# Frame2TTL_v3_0_0.net
KiCad netlist of a schematic drawn in EAGLE
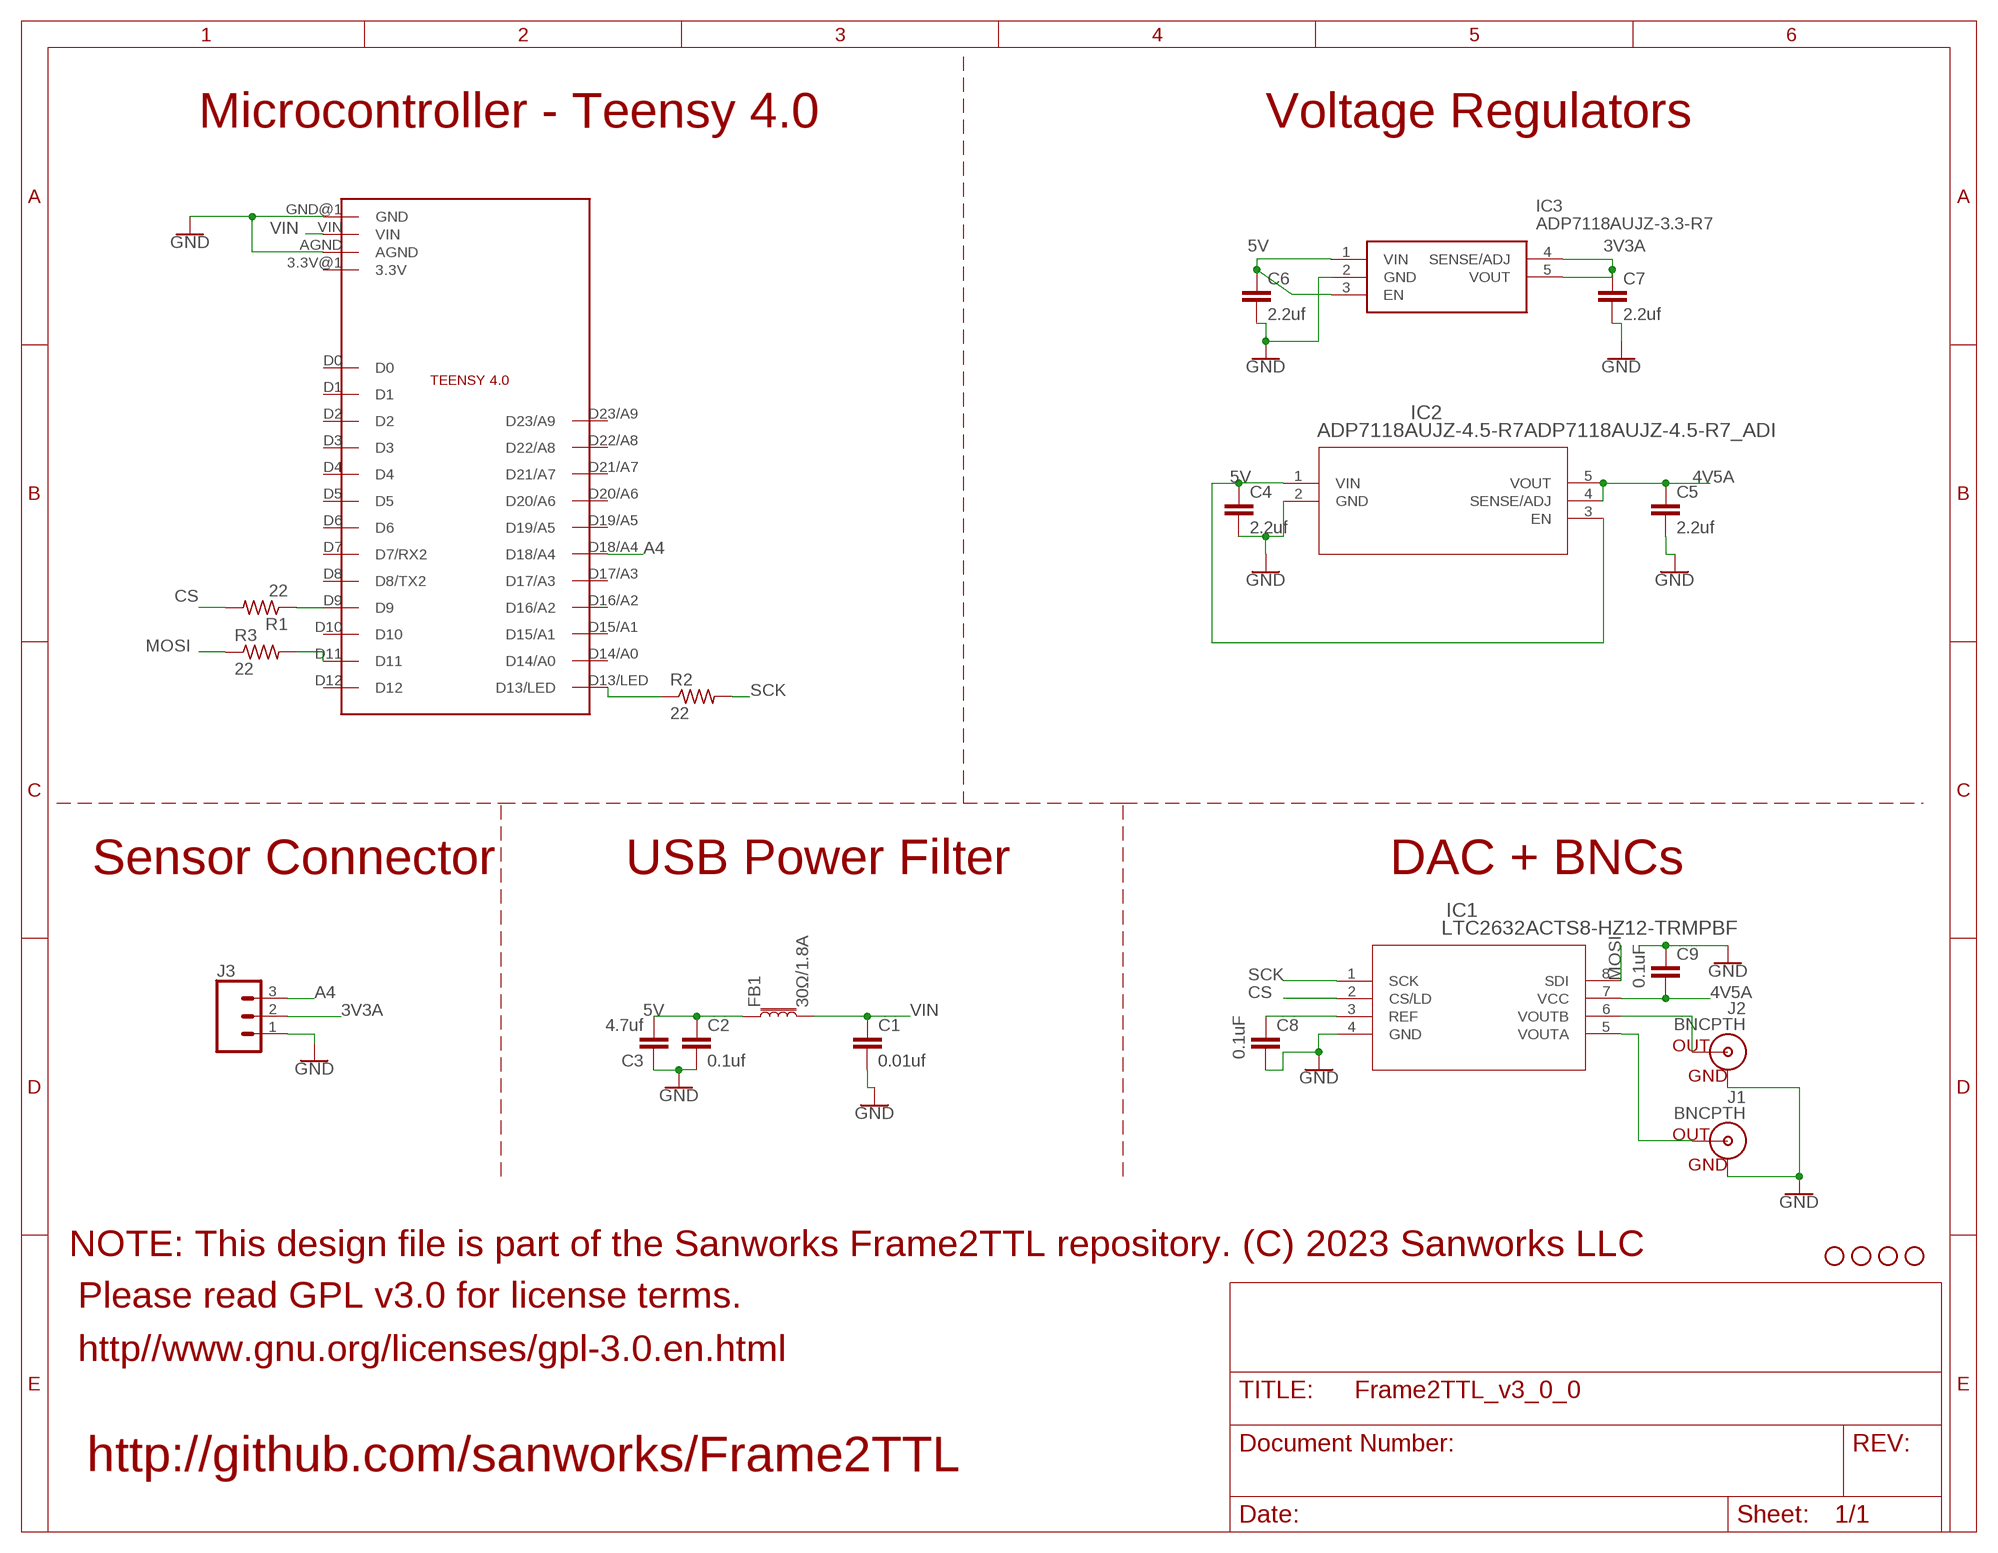
[diagram p0: schematic, sheet 1]

(export (version "E")
  (design (tool "Eeschema 10.0.6"))
  (components
    (comp (ref "C1")
      (value "0.01uf")
      (footprint "eagle-import:0805")
      (libsource (lib "eagle-import") (part "10UF-0805-10V-10%"))
    )
    (comp (ref "C2")
      (value "0.1uf")
      (footprint "eagle-import:0805")
      (libsource (lib "eagle-import") (part "10UF-0805-10V-10%"))
    )
    (comp (ref "C3")
      (value "4.7uf")
      (footprint "eagle-import:1206@2")
      (libsource (lib "eagle-import") (part "CAP1206"))
    )
    (comp (ref "C4")
      (value "2.2uf")
      (footprint "eagle-import:0805")
      (libsource (lib "eagle-import") (part "1.0UF-0805-25V-10%"))
    )
    (comp (ref "C5")
      (value "2.2uf")
      (footprint "eagle-import:0805")
      (libsource (lib "eagle-import") (part "1.0UF-0805-25V-10%"))
    )
    (comp (ref "C6")
      (value "2.2uf")
      (footprint "eagle-import:0805")
      (libsource (lib "eagle-import") (part "1.0UF-0805-25V-10%"))
    )
    (comp (ref "C7")
      (value "2.2uf")
      (footprint "eagle-import:0805")
      (libsource (lib "eagle-import") (part "1.0UF-0805-25V-10%"))
    )
    (comp (ref "C8")
      (value "0.1uF")
      (footprint "eagle-import:0805")
      (libsource (lib "eagle-import") (part "1.0UF-0805-25V-10%"))
    )
    (comp (ref "C9")
      (value "0.1uF")
      (footprint "eagle-import:0805")
      (libsource (lib "eagle-import") (part "1.0UF-0805-25V-10%"))
    )
    (comp (ref "FB1")
      (value "30Ω/1.8A")
      (footprint "eagle-import:0603")
      (libsource (lib "eagle-import") (part "FERRITE_BEAD-0603"))
    )
    (comp (ref "H1")
      (value "STAND-OFF")
      (footprint "eagle-import:STAND-OFF")
      (libsource (lib "eagle-import") (part "STAND-OFF"))
    )
    (comp (ref "H2")
      (value "STAND-OFF")
      (footprint "eagle-import:STAND-OFF")
      (libsource (lib "eagle-import") (part "STAND-OFF"))
    )
    (comp (ref "H3")
      (value "STAND-OFF")
      (footprint "eagle-import:STAND-OFF")
      (libsource (lib "eagle-import") (part "STAND-OFF"))
    )
    (comp (ref "H4")
      (value "STAND-OFF")
      (footprint "eagle-import:STAND-OFF")
      (libsource (lib "eagle-import") (part "STAND-OFF"))
    )
    (comp (ref "IC1")
      (value "LTC2632ACTS8-HZ12-TRMPBF")
      (footprint "eagle-import:TSOT-23-8_1P625X2P9_ADI")
      (fields
        (field (name "MANUFACTURER_PART_NUMBER") "LTC2632AHTS8-LI12#TRMPBF")
        (field (name "COPYRIGHT") "Copyright (C) 2022 Ultra Librarian. All rights reserved.")
      )
      (libsource (lib "eagle-import") (part "LTC2632AHTS8-LI12TRMPBF"))
    )
    (comp (ref "IC2")
      (value "ADP7118AUJZ-4.5-R7ADP7118AUJZ-4.5-R7_ADI")
      (footprint "eagle-import:ADP7118AUJZ-4.5-R7_ADI")
      (fields
        (field (name "MANUFACTURER_PART_NUMBER") "ADP7118AUJZ-4.5-R7")
        (field (name "COPYRIGHT") "Copyright (C) 2023 Ultra Librarian. All rights reserved.")
      )
      (libsource (lib "eagle-import") (part "ADP7118AUJZ-4.5-R7ADP7118AUJZ-4.5-R7_ADI"))
    )
    (comp (ref "IC3")
      (value "ADP7118AUJZ-3.3-R7")
      (footprint "eagle-import:SOT95P280X100-5N")
      (fields (field (name "MOUSER_PART_NUMBER") "584-ADP7118AUJZ3.3R7"))
      (libsource (lib "eagle-import") (part "ADP7118AUJZ-3.3-R7"))
    )
    (comp (ref "J1")
      (value "BNCPTH")
      (footprint "eagle-import:BNC")
      (libsource (lib "eagle-import") (part "BNCPTH"))
    )
    (comp (ref "J2")
      (value "BNCPTH")
      (footprint "eagle-import:BNC")
      (libsource (lib "eagle-import") (part "BNCPTH"))
    )
    (comp (ref "J3")
      (value "CONN_03LOCK")
      (footprint "eagle-import:1X03_LOCK")
      (libsource (lib "eagle-import") (part "CONN_03LOCK"))
    )
    (comp (ref "MC1")
      (value "TEENSY4.0_SIMPLE_NO_VUSB")
      (footprint "eagle-import:TEENSY4.0_SIMPLE_NO_VUSB")
      (libsource (lib "eagle-import") (part "TEENSY4.0_SIMPLE_NO_VUSB"))
    )
    (comp (ref "R1")
      (value "22")
      (footprint "eagle-import:R0805")
      (libsource (lib "eagle-import") (part "R-US_R0805"))
    )
    (comp (ref "R2")
      (value "22")
      (footprint "eagle-import:R0805")
      (libsource (lib "eagle-import") (part "R-US_R0805"))
    )
    (comp (ref "R3")
      (value "22")
      (footprint "eagle-import:R0805")
      (libsource (lib "eagle-import") (part "R-US_R0805"))
    )
  )
  (nets
    (net (code "1") (name "/3V3A") (class "Default")
      (node (ref "C7") (pin "1") (pinfunction "1_1") (pintype "passive"))
      (node (ref "IC3") (pin "4") (pinfunction "SENSE/ADJ_4") (pintype "bidirectional"))
      (node (ref "IC3") (pin "5") (pinfunction "VOUT_5") (pintype "bidirectional"))
      (node (ref "J3") (pin "2") (pinfunction "2_2") (pintype "passive"))
    )
    (net (code "2") (name "/4V5A") (class "Default")
      (node (ref "C5") (pin "1") (pinfunction "1_1") (pintype "passive"))
      (node (ref "C9") (pin "2") (pinfunction "2_2") (pintype "passive"))
      (node (ref "IC1") (pin "7") (pinfunction "VCC_7") (pintype "power_in"))
      (node (ref "IC2") (pin "4") (pinfunction "SENSE/ADJ_4") (pintype "input"))
      (node (ref "IC2") (pin "5") (pinfunction "VOUT_5") (pintype "passive"))
    )
    (net (code "3") (name "/5V") (class "Default")
      (node (ref "C2") (pin "1") (pinfunction "1_1") (pintype "passive"))
      (node (ref "C3") (pin "2") (pinfunction "2_2") (pintype "passive"))
      (node (ref "C4") (pin "1") (pinfunction "1_1") (pintype "passive"))
      (node (ref "C6") (pin "1") (pinfunction "1_1") (pintype "passive"))
      (node (ref "FB1") (pin "1") (pinfunction "1_1") (pintype "passive"))
      (node (ref "IC2") (pin "1") (pinfunction "VIN_1") (pintype "power_in"))
      (node (ref "IC2") (pin "3") (pinfunction "EN_3") (pintype "input"))
      (node (ref "IC3") (pin "1") (pinfunction "VIN_1") (pintype "bidirectional"))
      (node (ref "IC3") (pin "3") (pinfunction "EN_3") (pintype "bidirectional"))
    )
    (net (code "4") (name "/A4") (class "Default")
      (node (ref "J3") (pin "3") (pinfunction "3_3") (pintype "passive"))
      (node (ref "MC1") (pin "D18/A4") (pinfunction "D18/A4_D18/A4") (pintype "bidirectional"))
    )
    (net (code "5") (name "/CS") (class "Default")
      (node (ref "IC1") (pin "2") (pinfunction "CS/LD_2") (pintype "passive"))
      (node (ref "R1") (pin "2") (pinfunction "2_2") (pintype "passive"))
    )
    (net (code "6") (name "/MOSI") (class "Default")
      (node (ref "IC1") (pin "8") (pinfunction "SDI_8") (pintype "passive"))
      (node (ref "R3") (pin "1") (pinfunction "1_1") (pintype "passive"))
    )
    (net (code "7") (name "/SCK") (class "Default")
      (node (ref "IC1") (pin "1") (pinfunction "SCK_1") (pintype "passive"))
      (node (ref "R2") (pin "2") (pinfunction "2_2") (pintype "passive"))
    )
    (net (code "8") (name "/VIN") (class "Default")
      (node (ref "C1") (pin "1") (pinfunction "1_1") (pintype "passive"))
      (node (ref "FB1") (pin "2") (pinfunction "2_2") (pintype "passive"))
      (node (ref "MC1") (pin "VIN") (pinfunction "VIN_VIN") (pintype "bidirectional"))
    )
    (net (code "9") (name "GND") (class "Default")
      (node (ref "C1") (pin "2") (pinfunction "2_2") (pintype "passive"))
      (node (ref "C2") (pin "2") (pinfunction "2_2") (pintype "passive"))
      (node (ref "C3") (pin "1") (pinfunction "1_1") (pintype "passive"))
      (node (ref "C4") (pin "2") (pinfunction "2_2") (pintype "passive"))
      (node (ref "C5") (pin "2") (pinfunction "2_2") (pintype "passive"))
      (node (ref "C6") (pin "2") (pinfunction "2_2") (pintype "passive"))
      (node (ref "C7") (pin "2") (pinfunction "2_2") (pintype "passive"))
      (node (ref "C8") (pin "2") (pinfunction "2_2") (pintype "passive"))
      (node (ref "C9") (pin "1") (pinfunction "1_1") (pintype "passive"))
      (node (ref "IC1") (pin "4") (pinfunction "GND_4") (pintype "passive"))
      (node (ref "IC2") (pin "2") (pinfunction "GND_2") (pintype "passive"))
      (node (ref "IC3") (pin "2") (pinfunction "GND_2") (pintype "bidirectional"))
      (node (ref "J1") (pin "GND") (pinfunction "GND_GND") (pintype "bidirectional"))
      (node (ref "J2") (pin "GND") (pinfunction "GND_GND") (pintype "bidirectional"))
      (node (ref "J3") (pin "1") (pinfunction "1_1") (pintype "passive"))
      (node (ref "MC1") (pin "AGND") (pinfunction "AGND_AGND") (pintype "bidirectional"))
      (node (ref "MC1") (pin "GND@1") (pinfunction "GND_GND@1") (pintype "bidirectional"))
    )
    (net (code "10") (name "Net-(IC1-REF)") (class "Default")
      (node (ref "C8") (pin "1") (pinfunction "1_1") (pintype "passive"))
      (node (ref "IC1") (pin "3") (pinfunction "REF_3") (pintype "passive"))
    )
    (net (code "11") (name "Net-(IC1-VOUTA)") (class "Default")
      (node (ref "IC1") (pin "5") (pinfunction "VOUTA_5") (pintype "output"))
      (node (ref "J1") (pin "S") (pinfunction "OUT_S") (pintype "bidirectional"))
    )
    (net (code "12") (name "Net-(IC1-VOUTB)") (class "Default")
      (node (ref "IC1") (pin "6") (pinfunction "VOUTB_6") (pintype "output"))
      (node (ref "J2") (pin "S") (pinfunction "OUT_S") (pintype "bidirectional"))
    )
    (net (code "13") (name "Net-(MC1-PadD9)") (class "Default")
      (node (ref "MC1") (pin "D9") (pinfunction "D9_D9") (pintype "bidirectional"))
      (node (ref "R1") (pin "1") (pinfunction "1_1") (pintype "passive"))
    )
    (net (code "14") (name "Net-(MC1-PadD11)") (class "Default")
      (node (ref "MC1") (pin "D11") (pinfunction "D11_D11") (pintype "bidirectional"))
      (node (ref "R3") (pin "2") (pinfunction "2_2") (pintype "passive"))
    )
    (net (code "15") (name "Net-(MC1-PadD13{slash}LED)") (class "Default")
      (node (ref "MC1") (pin "D13/LED") (pinfunction "D13/LED_D13/LED") (pintype "bidirectional"))
      (node (ref "R2") (pin "1") (pinfunction "1_1") (pintype "passive"))
    )
    (net (code "16") (name "unconnected-(MC1-3.3V-Pad3.3V@1)") (class "Default")
      (node (ref "MC1") (pin "3.3V@1") (pinfunction "3.3V_3.3V@1") (pintype "bidirectional"))
    )
    (net (code "17") (name "unconnected-(MC1-D7{slash}RX2-PadD7)") (class "Default")
      (node (ref "MC1") (pin "D7") (pinfunction "D7/RX2_D7") (pintype "bidirectional"))
    )
    (net (code "18") (name "unconnected-(MC1-D8{slash}TX2-PadD8)") (class "Default")
      (node (ref "MC1") (pin "D8") (pinfunction "D8/TX2_D8") (pintype "bidirectional"))
    )
    (net (code "19") (name "unconnected-(MC1-PadD0)") (class "Default")
      (node (ref "MC1") (pin "D0") (pinfunction "D0_D0") (pintype "bidirectional"))
    )
    (net (code "20") (name "unconnected-(MC1-PadD1)") (class "Default")
      (node (ref "MC1") (pin "D1") (pinfunction "D1_D1") (pintype "bidirectional"))
    )
    (net (code "21") (name "unconnected-(MC1-PadD2)") (class "Default")
      (node (ref "MC1") (pin "D2") (pinfunction "D2_D2") (pintype "bidirectional"))
    )
    (net (code "22") (name "unconnected-(MC1-PadD3)") (class "Default")
      (node (ref "MC1") (pin "D3") (pinfunction "D3_D3") (pintype "bidirectional"))
    )
    (net (code "23") (name "unconnected-(MC1-PadD4)") (class "Default")
      (node (ref "MC1") (pin "D4") (pinfunction "D4_D4") (pintype "bidirectional"))
    )
    (net (code "24") (name "unconnected-(MC1-PadD5)") (class "Default")
      (node (ref "MC1") (pin "D5") (pinfunction "D5_D5") (pintype "bidirectional"))
    )
    (net (code "25") (name "unconnected-(MC1-PadD6)") (class "Default")
      (node (ref "MC1") (pin "D6") (pinfunction "D6_D6") (pintype "bidirectional"))
    )
    (net (code "26") (name "unconnected-(MC1-PadD10)") (class "Default")
      (node (ref "MC1") (pin "D10") (pinfunction "D10_D10") (pintype "bidirectional"))
    )
    (net (code "27") (name "unconnected-(MC1-PadD12)") (class "Default")
      (node (ref "MC1") (pin "D12") (pinfunction "D12_D12") (pintype "bidirectional"))
    )
    (net (code "28") (name "unconnected-(MC1-PadD14{slash}A0)") (class "Default")
      (node (ref "MC1") (pin "D14/A0") (pinfunction "D14/A0_D14/A0") (pintype "bidirectional"))
    )
    (net (code "29") (name "unconnected-(MC1-PadD15{slash}A1)") (class "Default")
      (node (ref "MC1") (pin "D15/A1") (pinfunction "D15/A1_D15/A1") (pintype "bidirectional"))
    )
    (net (code "30") (name "unconnected-(MC1-PadD16{slash}A2)") (class "Default")
      (node (ref "MC1") (pin "D16/A2") (pinfunction "D16/A2_D16/A2") (pintype "bidirectional"))
    )
    (net (code "31") (name "unconnected-(MC1-PadD17{slash}A3)") (class "Default")
      (node (ref "MC1") (pin "D17/A3") (pinfunction "D17/A3_D17/A3") (pintype "bidirectional"))
    )
    (net (code "32") (name "unconnected-(MC1-PadD19{slash}A5)") (class "Default")
      (node (ref "MC1") (pin "D19/A5") (pinfunction "D19/A5_D19/A5") (pintype "bidirectional"))
    )
    (net (code "33") (name "unconnected-(MC1-PadD20{slash}A6)") (class "Default")
      (node (ref "MC1") (pin "D20/A6") (pinfunction "D20/A6_D20/A6") (pintype "bidirectional"))
    )
    (net (code "34") (name "unconnected-(MC1-PadD21{slash}A7)") (class "Default")
      (node (ref "MC1") (pin "D21/A7") (pinfunction "D21/A7_D21/A7") (pintype "bidirectional"))
    )
    (net (code "35") (name "unconnected-(MC1-PadD22{slash}A8)") (class "Default")
      (node (ref "MC1") (pin "D22/A8") (pinfunction "D22/A8_D22/A8") (pintype "bidirectional"))
    )
    (net (code "36") (name "unconnected-(MC1-PadD23{slash}A9)") (class "Default")
      (node (ref "MC1") (pin "D23/A9") (pinfunction "D23/A9_D23/A9") (pintype "bidirectional"))
    )
  )
)
